# FAN-zero-SHIM.net
KiCad netlist of a schematic drawn in EAGLE
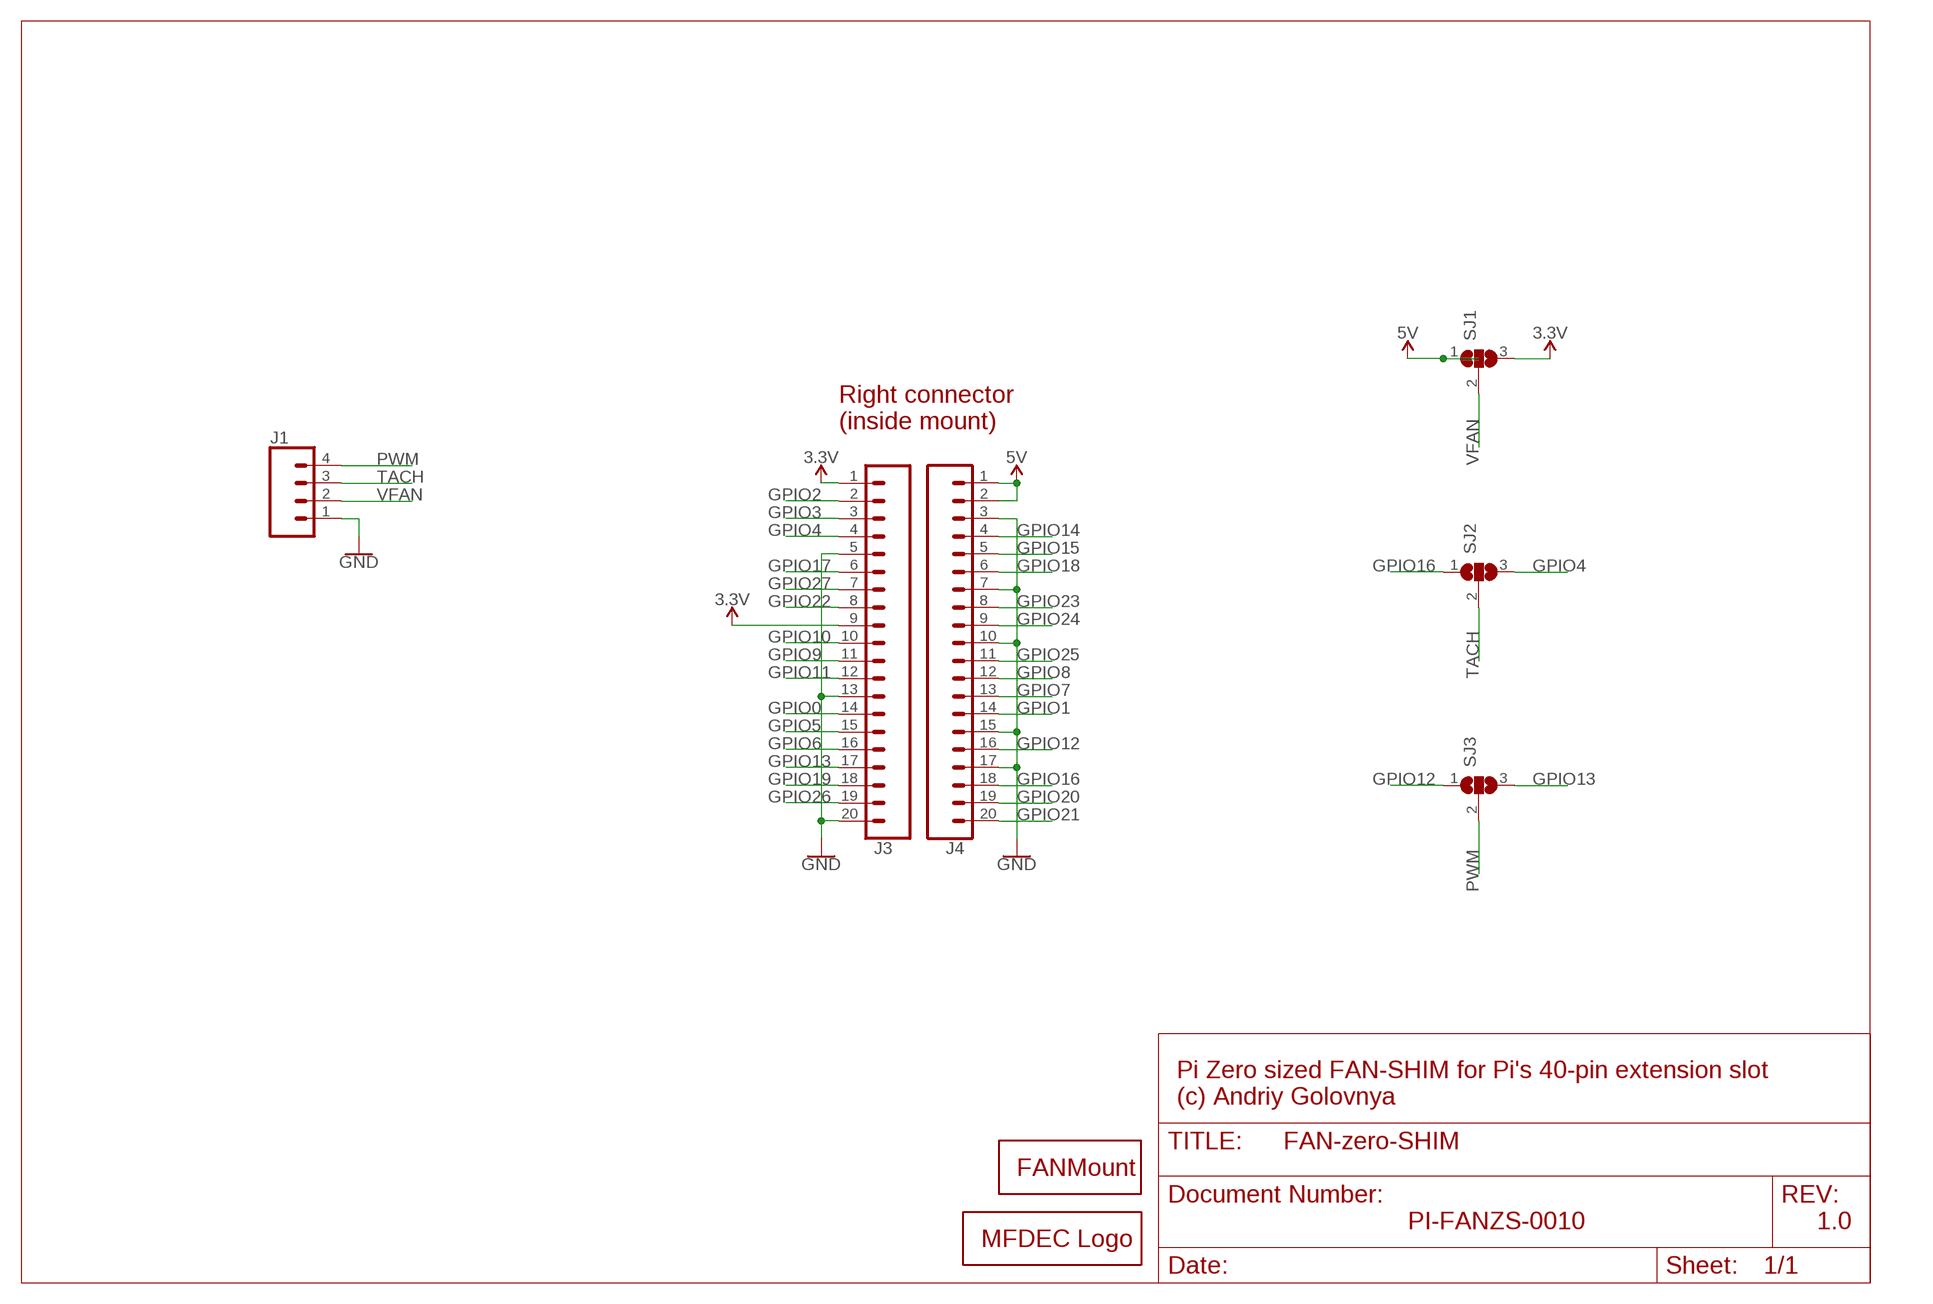
[diagram p0: schematic, sheet 1]

(export (version "E")
  (design (tool "Eeschema 10.0.6"))
  (components
    (comp (ref "FAN1")
      (value "FAN30HO")
      (footprint "eagle-import:FAN30HO")
      (libsource (lib "eagle-import") (part "FAN30HO"))
    )
    (comp (ref "J1")
      (value "CONN_04")
      (footprint "eagle-import:1X04")
      (libsource (lib "eagle-import") (part "CONN_04"))
    )
    (comp (ref "J3")
      (value "CONN_20LOCK")
      (footprint "eagle-import:1X20_LOCK")
      (libsource (lib "eagle-import") (part "CONN_20LOCK"))
    )
    (comp (ref "J4")
      (value "CONN_20LOCK")
      (footprint "eagle-import:1X20_LOCK")
      (libsource (lib "eagle-import") (part "CONN_20LOCK"))
    )
    (comp (ref "LOGO1")
      (value "MFDECLOGO_L_30MM")
      (footprint "eagle-import:MFDEC_L_30MM")
      (libsource (lib "eagle-import") (part "MFDECLOGO_L_30MM"))
    )
    (comp (ref "SJ1")
      (value "SJ2")
      (footprint "eagle-import:SJ_2")
      (libsource (lib "eagle-import") (part "SJ2"))
    )
    (comp (ref "SJ2")
      (value "SJ2")
      (footprint "eagle-import:SJ_2")
      (libsource (lib "eagle-import") (part "SJ2"))
    )
    (comp (ref "SJ3")
      (value "SJ2")
      (footprint "eagle-import:SJ_2")
      (libsource (lib "eagle-import") (part "SJ2"))
    )
  )
  (nets
    (net (code "1") (name "/GPIO0") (class "Default")
      (node (ref "J3") (pin "14") (pinfunction "14_14") (pintype "passive"))
    )
    (net (code "2") (name "/GPIO1") (class "Default")
      (node (ref "J4") (pin "14") (pinfunction "14_14") (pintype "passive"))
    )
    (net (code "3") (name "/GPIO2") (class "Default")
      (node (ref "J3") (pin "2") (pinfunction "2_2") (pintype "passive"))
    )
    (net (code "4") (name "/GPIO3") (class "Default")
      (node (ref "J3") (pin "3") (pinfunction "3_3") (pintype "passive"))
    )
    (net (code "5") (name "/GPIO4") (class "Default")
      (node (ref "J3") (pin "4") (pinfunction "4_4") (pintype "passive"))
      (node (ref "SJ2") (pin "3") (pinfunction "3_3") (pintype "passive"))
    )
    (net (code "6") (name "/GPIO5") (class "Default")
      (node (ref "J3") (pin "15") (pinfunction "15_15") (pintype "passive"))
    )
    (net (code "7") (name "/GPIO6") (class "Default")
      (node (ref "J3") (pin "16") (pinfunction "16_16") (pintype "passive"))
    )
    (net (code "8") (name "/GPIO7") (class "Default")
      (node (ref "J4") (pin "13") (pinfunction "13_13") (pintype "passive"))
    )
    (net (code "9") (name "/GPIO8") (class "Default")
      (node (ref "J4") (pin "12") (pinfunction "12_12") (pintype "passive"))
    )
    (net (code "10") (name "/GPIO9") (class "Default")
      (node (ref "J3") (pin "11") (pinfunction "11_11") (pintype "passive"))
    )
    (net (code "11") (name "/GPIO10") (class "Default")
      (node (ref "J3") (pin "10") (pinfunction "10_10") (pintype "passive"))
    )
    (net (code "12") (name "/GPIO11") (class "Default")
      (node (ref "J3") (pin "12") (pinfunction "12_12") (pintype "passive"))
    )
    (net (code "13") (name "/GPIO12") (class "Default")
      (node (ref "J4") (pin "16") (pinfunction "16_16") (pintype "passive"))
      (node (ref "SJ3") (pin "1") (pinfunction "1_1") (pintype "passive"))
    )
    (net (code "14") (name "/GPIO13") (class "Default")
      (node (ref "J3") (pin "17") (pinfunction "17_17") (pintype "passive"))
      (node (ref "SJ3") (pin "3") (pinfunction "3_3") (pintype "passive"))
    )
    (net (code "15") (name "/GPIO14") (class "Default")
      (node (ref "J4") (pin "4") (pinfunction "4_4") (pintype "passive"))
    )
    (net (code "16") (name "/GPIO15") (class "Default")
      (node (ref "J4") (pin "5") (pinfunction "5_5") (pintype "passive"))
    )
    (net (code "17") (name "/GPIO16") (class "Default")
      (node (ref "J4") (pin "18") (pinfunction "18_18") (pintype "passive"))
      (node (ref "SJ2") (pin "1") (pinfunction "1_1") (pintype "passive"))
    )
    (net (code "18") (name "/GPIO17") (class "Default")
      (node (ref "J3") (pin "6") (pinfunction "6_6") (pintype "passive"))
    )
    (net (code "19") (name "/GPIO18") (class "Default")
      (node (ref "J4") (pin "6") (pinfunction "6_6") (pintype "passive"))
    )
    (net (code "20") (name "/GPIO19") (class "Default")
      (node (ref "J3") (pin "18") (pinfunction "18_18") (pintype "passive"))
    )
    (net (code "21") (name "/GPIO20") (class "Default")
      (node (ref "J4") (pin "19") (pinfunction "19_19") (pintype "passive"))
    )
    (net (code "22") (name "/GPIO21") (class "Default")
      (node (ref "J4") (pin "20") (pinfunction "20_20") (pintype "passive"))
    )
    (net (code "23") (name "/GPIO22") (class "Default")
      (node (ref "J3") (pin "8") (pinfunction "8_8") (pintype "passive"))
    )
    (net (code "24") (name "/GPIO23") (class "Default")
      (node (ref "J4") (pin "8") (pinfunction "8_8") (pintype "passive"))
    )
    (net (code "25") (name "/GPIO24") (class "Default")
      (node (ref "J4") (pin "9") (pinfunction "9_9") (pintype "passive"))
    )
    (net (code "26") (name "/GPIO25") (class "Default")
      (node (ref "J4") (pin "11") (pinfunction "11_11") (pintype "passive"))
    )
    (net (code "27") (name "/GPIO26") (class "Default")
      (node (ref "J3") (pin "19") (pinfunction "19_19") (pintype "passive"))
    )
    (net (code "28") (name "/GPIO27") (class "Default")
      (node (ref "J3") (pin "7") (pinfunction "7_7") (pintype "passive"))
    )
    (net (code "29") (name "/PWM") (class "Default")
      (node (ref "J1") (pin "4") (pinfunction "4_4") (pintype "passive"))
      (node (ref "SJ3") (pin "2") (pinfunction "2_2") (pintype "passive"))
    )
    (net (code "30") (name "/TACH") (class "Default")
      (node (ref "J1") (pin "3") (pinfunction "3_3") (pintype "passive"))
      (node (ref "SJ2") (pin "2") (pinfunction "2_2") (pintype "passive"))
    )
    (net (code "31") (name "/VFAN") (class "Default")
      (node (ref "J1") (pin "2") (pinfunction "2_2") (pintype "passive"))
      (node (ref "SJ1") (pin "2") (pinfunction "2_2") (pintype "passive"))
    )
    (net (code "32") (name "3.3V") (class "Default")
      (node (ref "J3") (pin "1") (pinfunction "1_1") (pintype "passive"))
      (node (ref "J3") (pin "9") (pinfunction "9_9") (pintype "passive"))
      (node (ref "SJ1") (pin "3") (pinfunction "3_3") (pintype "passive"))
    )
    (net (code "33") (name "5V") (class "Default")
      (node (ref "J4") (pin "1") (pinfunction "1_1") (pintype "passive"))
      (node (ref "J4") (pin "2") (pinfunction "2_2") (pintype "passive"))
      (node (ref "SJ1") (pin "1") (pinfunction "1_1") (pintype "passive"))
    )
    (net (code "34") (name "GND") (class "Default")
      (node (ref "J1") (pin "1") (pinfunction "1_1") (pintype "passive"))
      (node (ref "J3") (pin "13") (pinfunction "13_13") (pintype "passive"))
      (node (ref "J3") (pin "20") (pinfunction "20_20") (pintype "passive"))
      (node (ref "J3") (pin "5") (pinfunction "5_5") (pintype "passive"))
      (node (ref "J4") (pin "10") (pinfunction "10_10") (pintype "passive"))
      (node (ref "J4") (pin "15") (pinfunction "15_15") (pintype "passive"))
      (node (ref "J4") (pin "17") (pinfunction "17_17") (pintype "passive"))
      (node (ref "J4") (pin "3") (pinfunction "3_3") (pintype "passive"))
      (node (ref "J4") (pin "7") (pinfunction "7_7") (pintype "passive"))
    )
  )
)
